# VentaConnected_Arduino_V0_01_2017-11-21.net
KiCad netlist of a schematic drawn in EAGLE
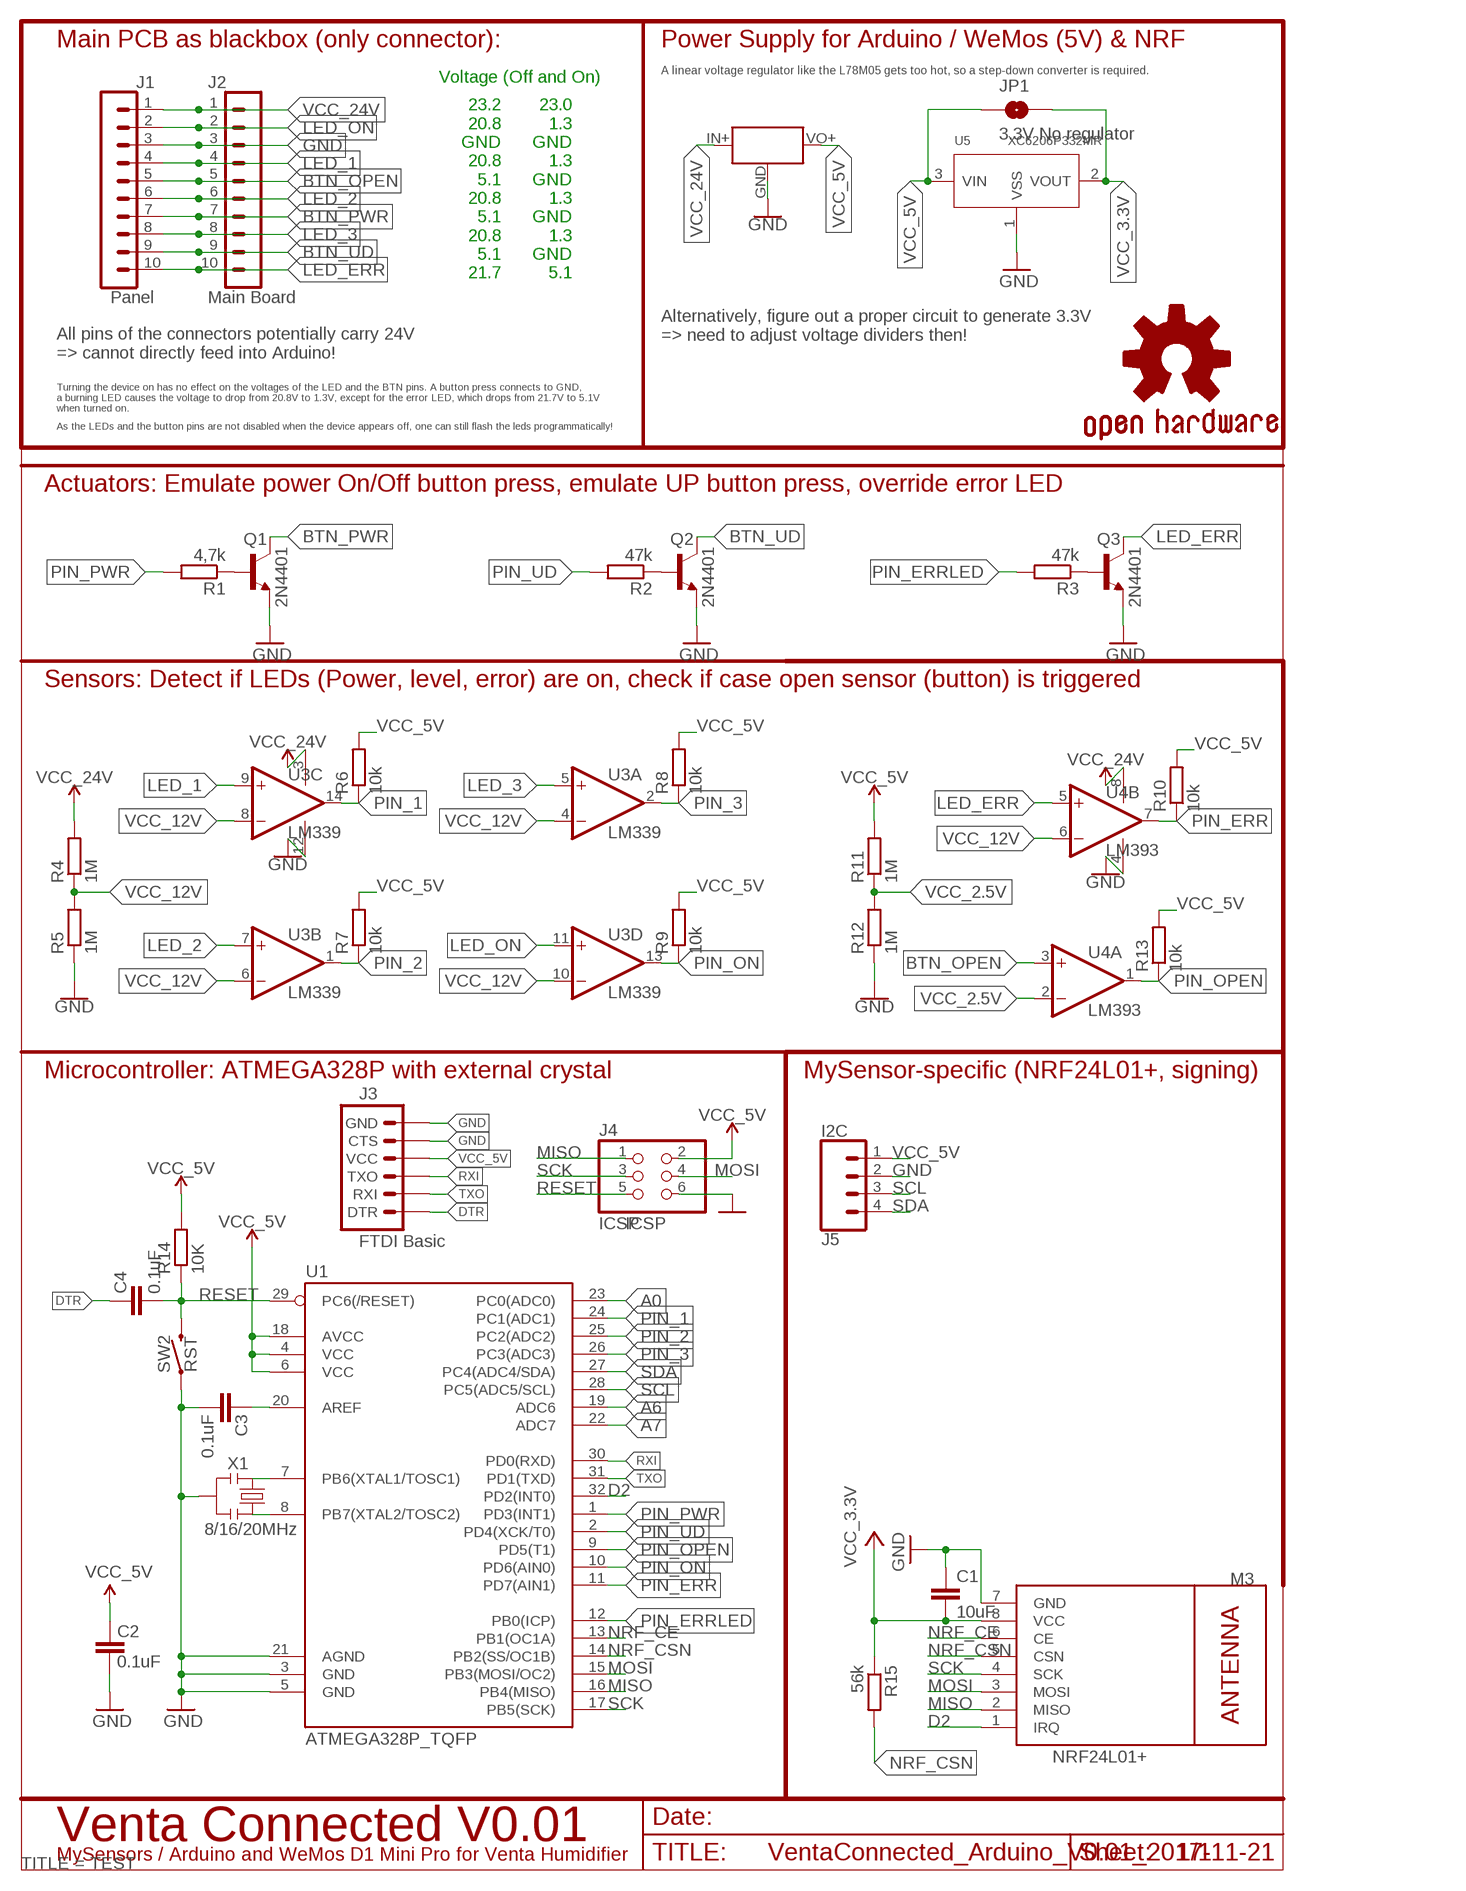
[diagram p0: schematic, sheet 1]

(export (version "E")
  (design (tool "Eeschema 10.0.6"))
  (components
    (comp (ref "C1")
      (value "10uF")
      (footprint "eagle-import:C0805")
      (libsource (lib "eagle-import") (part "C-EUC0805"))
    )
    (comp (ref "C2")
      (value "0.1uF")
      (footprint "eagle-import:0805")
      (libsource (lib "eagle-import") (part "CAP0805"))
    )
    (comp (ref "C3")
      (value "0.1uF")
      (footprint "eagle-import:0805")
      (libsource (lib "eagle-import") (part "CAP0805"))
    )
    (comp (ref "C4")
      (value "0.1uF")
      (footprint "eagle-import:0805")
      (libsource (lib "eagle-import") (part "CAP0805"))
    )
    (comp (ref "GOLD_ORB_SM1")
      (value "OSHWLOGO_GOLD_ORB_SM")
      (footprint "eagle-import:OSHW2")
      (libsource (lib "eagle-import") (part "OSHWLOGO_GOLD_ORB_SM"))
    )
    (comp (ref "J1")
      (value "Panel")
      (footprint "eagle-import:2X5-SHROUDED")
      (libsource (lib "eagle-import") (part "CONN_05X2SHD"))
    )
    (comp (ref "J2")
      (value "Main Board")
      (footprint "eagle-import:2X5")
      (libsource (lib "eagle-import") (part "CONN_05X2PTH"))
    )
    (comp (ref "J3")
      (value "FTDI Basic")
      (footprint "eagle-import:1X06")
      (libsource (lib "eagle-import") (part "ARDUINO_SERIAL_PROGRAMPTH"))
    )
    (comp (ref "J4")
      (value "ICSP")
      (footprint "eagle-import:2X03")
      (libsource (lib "eagle-import") (part "PINHD-2X3"))
    )
    (comp (ref "J5")
      (value "I2C")
      (footprint "eagle-import:1X04")
      (libsource (lib "eagle-import") (part "CONN_04"))
    )
    (comp (ref "JP1")
      (value "3.3V No regulator")
      (footprint "eagle-import:SMT-JUMPER_2_NO_SILK")
      (libsource (lib "eagle-import") (part "JUMPER-SMT_2_NO_SILK"))
    )
    (comp (ref "M3")
      (value "NRF24L01+")
      (footprint "eagle-import:WIRELESS-NRF24L01-SMD")
      (libsource (lib "eagle-import") (part "WIRELESS-NRF24L01SMD"))
    )
    (comp (ref "Q1")
      (value "2N4401")
      (footprint "eagle-import:SOT23-BEC")
      (libsource (lib "eagle-import") (part "-NPN-SOT23-BECMMBT4401LT1"))
    )
    (comp (ref "Q2")
      (value "2N4401")
      (footprint "eagle-import:SOT23-BEC")
      (libsource (lib "eagle-import") (part "-NPN-SOT23-BECMMBT4401LT1"))
    )
    (comp (ref "Q3")
      (value "2N4401")
      (footprint "eagle-import:SOT23-BEC")
      (libsource (lib "eagle-import") (part "-NPN-SOT23-BECMMBT4401LT1"))
    )
    (comp (ref "R1")
      (value "4,7k")
      (footprint "eagle-import:R0805")
      (libsource (lib "eagle-import") (part "resistor_348_R-EU_R0805"))
    )
    (comp (ref "R2")
      (value "47k")
      (footprint "eagle-import:R0805")
      (libsource (lib "eagle-import") (part "resistor_348_R-EU_R0805"))
    )
    (comp (ref "R3")
      (value "47k")
      (footprint "eagle-import:R0805")
      (libsource (lib "eagle-import") (part "resistor_348_R-EU_R0805"))
    )
    (comp (ref "R4")
      (value "1M")
      (footprint "eagle-import:R0805")
      (libsource (lib "eagle-import") (part "resistor_348_R-EU_R0805"))
    )
    (comp (ref "R5")
      (value "1M")
      (footprint "eagle-import:R0805")
      (libsource (lib "eagle-import") (part "resistor_348_R-EU_R0805"))
    )
    (comp (ref "R6")
      (value "10k")
      (footprint "eagle-import:R0805")
      (libsource (lib "eagle-import") (part "rcl_334_R-EU_R0805"))
    )
    (comp (ref "R7")
      (value "10k")
      (footprint "eagle-import:R0805")
      (libsource (lib "eagle-import") (part "rcl_334_R-EU_R0805"))
    )
    (comp (ref "R8")
      (value "10k")
      (footprint "eagle-import:R0805")
      (libsource (lib "eagle-import") (part "rcl_334_R-EU_R0805"))
    )
    (comp (ref "R9")
      (value "10k")
      (footprint "eagle-import:R0805")
      (libsource (lib "eagle-import") (part "rcl_334_R-EU_R0805"))
    )
    (comp (ref "R10")
      (value "10k")
      (footprint "eagle-import:R0805")
      (libsource (lib "eagle-import") (part "rcl_334_R-EU_R0805"))
    )
    (comp (ref "R11")
      (value "1M")
      (footprint "eagle-import:R0805")
      (libsource (lib "eagle-import") (part "resistor_348_R-EU_R0805"))
    )
    (comp (ref "R12")
      (value "1M")
      (footprint "eagle-import:R0805")
      (libsource (lib "eagle-import") (part "resistor_348_R-EU_R0805"))
    )
    (comp (ref "R13")
      (value "10k")
      (footprint "eagle-import:R0805")
      (libsource (lib "eagle-import") (part "rcl_334_R-EU_R0805"))
    )
    (comp (ref "R14")
      (value "10K")
      (footprint "eagle-import:R0805")
      (libsource (lib "eagle-import") (part "rcl_334_R-EU_R0805"))
    )
    (comp (ref "R15")
      (value "56k")
      (footprint "eagle-import:R0805")
      (libsource (lib "eagle-import") (part "R-EU_R0805"))
    )
    (comp (ref "SW2")
      (value "RST")
      (footprint "eagle-import:TACTILE_SWITCH_SMD_6.0X3.5MM")
      (libsource (lib "eagle-import") (part "MOMENTARY-SWITCH-SPST-SMD-6.0X3.5MM"))
    )
    (comp (ref "U1")
      (value "ATMEGA328P_TQFP")
      (footprint "eagle-import:TQFP32-08")
      (libsource (lib "eagle-import") (part "ATMEGA328P_TQFP"))
    )
    (comp (ref "U2")
      (value "MINI_BUCK_CONVERTER_UPSIDEDOWN")
      (footprint "eagle-import:MINI_BUCK_CONVERTER_UPDOWN")
      (libsource (lib "eagle-import") (part "MINI_BUCK_CONVERTER_UPSIDEDOWN"))
    )
    (comp (ref "U3")
      (value "LM339")
      (footprint "eagle-import:SO14")
      (libsource (lib "eagle-import") (part "TLC339D"))
    )
    (comp (ref "U4")
      (value "LM393")
      (footprint "eagle-import:SO08")
      (libsource (lib "eagle-import") (part "LM393D"))
    )
    (comp (ref "U5")
      (value "XC6206P332MR")
      (footprint "eagle-import:SOT-23")
      (fields (field (name "MPN") "XC6206P332MR-G"))
      (libsource (lib "eagle-import") (part "PMIC-LDO-XC6206P332MR-G(SOT23)"))
    )
    (comp (ref "X1")
      (value "8/16/20MHz")
      (footprint "eagle-import:RESONATOR-SMD-1_1")
      (libsource (lib "eagle-import") (part "RESONATOR1{colon}1"))
    )
  )
  (nets
    (net (code "1") (name "/D2") (class "Default")
      (node (ref "M3") (pin "1") (pinfunction "IRQ_1") (pintype "bidirectional"))
      (node (ref "U1") (pin "32") (pinfunction "PD2(INT0)_32") (pintype "bidirectional"))
    )
    (net (code "2") (name "/MISO") (class "Default")
      (node (ref "J4") (pin "1") (pinfunction "1_1") (pintype "passive"))
      (node (ref "M3") (pin "2") (pinfunction "MISO_2") (pintype "bidirectional"))
      (node (ref "U1") (pin "16") (pinfunction "PB4(MISO)_16") (pintype "bidirectional"))
    )
    (net (code "3") (name "/MOSI") (class "Default")
      (node (ref "J4") (pin "4") (pinfunction "4_4") (pintype "passive"))
      (node (ref "M3") (pin "3") (pinfunction "MOSI_3") (pintype "bidirectional"))
      (node (ref "U1") (pin "15") (pinfunction "PB3(MOSI/OC2)_15") (pintype "bidirectional"))
    )
    (net (code "4") (name "/NRF_CE") (class "Default")
      (node (ref "M3") (pin "6") (pinfunction "CE_6") (pintype "bidirectional"))
      (node (ref "U1") (pin "13") (pinfunction "PB1(OC1A)_13") (pintype "bidirectional"))
    )
    (net (code "5") (name "/RESET") (class "Default")
      (node (ref "C4") (pin "1") (pinfunction "1_1") (pintype "passive"))
      (node (ref "J4") (pin "5") (pinfunction "5_5") (pintype "passive"))
      (node (ref "R14") (pin "1") (pinfunction "1_1") (pintype "passive"))
      (node (ref "SW2") (pin "2") (pinfunction "2_2") (pintype "passive"))
      (node (ref "U1") (pin "29") (pinfunction "PC6(/RESET)_29") (pintype "bidirectional"))
    )
    (net (code "6") (name "/SCK") (class "Default")
      (node (ref "J4") (pin "3") (pinfunction "3_3") (pintype "passive"))
      (node (ref "M3") (pin "4") (pinfunction "SCK_4") (pintype "bidirectional"))
      (node (ref "U1") (pin "17") (pinfunction "PB5(SCK)_17") (pintype "bidirectional"))
    )
    (net (code "7") (name "A0") (class "Default")
      (node (ref "U1") (pin "23") (pinfunction "PC0(ADC0)_23") (pintype "bidirectional"))
    )
    (net (code "8") (name "A6") (class "Default")
      (node (ref "U1") (pin "19") (pinfunction "ADC6_19") (pintype "bidirectional"))
    )
    (net (code "9") (name "A7") (class "Default")
      (node (ref "U1") (pin "22") (pinfunction "ADC7_22") (pintype "bidirectional"))
    )
    (net (code "10") (name "BTN_OPEN") (class "Default")
      (node (ref "J1") (pin "5") (pinfunction "5_5") (pintype "passive"))
      (node (ref "J2") (pin "5") (pinfunction "5_5") (pintype "passive"))
      (node (ref "U4") (pin "3") (pinfunction "+IN_3") (pintype "input"))
    )
    (net (code "11") (name "BTN_PWR") (class "Default")
      (node (ref "J1") (pin "7") (pinfunction "7_7") (pintype "passive"))
      (node (ref "J2") (pin "7") (pinfunction "7_7") (pintype "passive"))
      (node (ref "Q1") (pin "C") (pinfunction "C_C") (pintype "passive"))
    )
    (net (code "12") (name "BTN_UD") (class "Default")
      (node (ref "J1") (pin "9") (pinfunction "9_9") (pintype "passive"))
      (node (ref "J2") (pin "9") (pinfunction "9_9") (pintype "passive"))
      (node (ref "Q2") (pin "C") (pinfunction "C_C") (pintype "passive"))
    )
    (net (code "13") (name "DTR") (class "Default")
      (node (ref "C4") (pin "2") (pinfunction "2_2") (pintype "passive"))
      (node (ref "J3") (pin "1") (pinfunction "DTR_1") (pintype "passive"))
    )
    (net (code "14") (name "GND") (class "Default")
      (node (ref "C1") (pin "1") (pinfunction "1_1") (pintype "passive"))
      (node (ref "C2") (pin "1") (pinfunction "1_1") (pintype "passive"))
      (node (ref "C3") (pin "1") (pinfunction "1_1") (pintype "passive"))
      (node (ref "J1") (pin "3") (pinfunction "3_3") (pintype "passive"))
      (node (ref "J2") (pin "3") (pinfunction "3_3") (pintype "passive"))
      (node (ref "J3") (pin "5") (pinfunction "CTS_5") (pintype "passive"))
      (node (ref "J3") (pin "6") (pinfunction "GND_6") (pintype "passive"))
      (node (ref "J4") (pin "6") (pinfunction "6_6") (pintype "passive"))
      (node (ref "J5") (pin "2") (pinfunction "2_2") (pintype "passive"))
      (node (ref "M3") (pin "7") (pinfunction "GND_7") (pintype "power_in"))
      (node (ref "Q1") (pin "E") (pinfunction "E_E") (pintype "passive"))
      (node (ref "Q2") (pin "E") (pinfunction "E_E") (pintype "passive"))
      (node (ref "Q3") (pin "E") (pinfunction "E_E") (pintype "passive"))
      (node (ref "R12") (pin "1") (pinfunction "1_1") (pintype "passive"))
      (node (ref "R5") (pin "1") (pinfunction "1_1") (pintype "passive"))
      (node (ref "SW2") (pin "1") (pinfunction "1_1") (pintype "passive"))
      (node (ref "U1") (pin "21") (pinfunction "AGND_21") (pintype "bidirectional"))
      (node (ref "U1") (pin "3") (pinfunction "GND_3") (pintype "bidirectional"))
      (node (ref "U1") (pin "5") (pinfunction "GND_5") (pintype "bidirectional"))
      (node (ref "U2") (pin "GND") (pinfunction "GND_GND") (pintype "bidirectional"))
      (node (ref "U3") (pin "12") (pinfunction "V-_12") (pintype "power_in"))
      (node (ref "U4") (pin "4") (pinfunction "V-_4") (pintype "power_in"))
      (node (ref "U5") (pin "1") (pinfunction "VSS_1") (pintype "power_in"))
      (node (ref "X1") (pin "2") (pinfunction "2_2") (pintype "passive"))
    )
    (net (code "15") (name "LED_1") (class "Default")
      (node (ref "J1") (pin "4") (pinfunction "4_4") (pintype "passive"))
      (node (ref "J2") (pin "4") (pinfunction "4_4") (pintype "passive"))
      (node (ref "U3") (pin "9") (pinfunction "+IN_9") (pintype "input"))
    )
    (net (code "16") (name "LED_2") (class "Default")
      (node (ref "J1") (pin "6") (pinfunction "6_6") (pintype "passive"))
      (node (ref "J2") (pin "6") (pinfunction "6_6") (pintype "passive"))
      (node (ref "U3") (pin "7") (pinfunction "+IN_7") (pintype "input"))
    )
    (net (code "17") (name "LED_3") (class "Default")
      (node (ref "J1") (pin "8") (pinfunction "8_8") (pintype "passive"))
      (node (ref "J2") (pin "8") (pinfunction "8_8") (pintype "passive"))
      (node (ref "U3") (pin "5") (pinfunction "+IN_5") (pintype "input"))
    )
    (net (code "18") (name "LED_ERR") (class "Default")
      (node (ref "J1") (pin "10") (pinfunction "10_10") (pintype "passive"))
      (node (ref "J2") (pin "10") (pinfunction "10_10") (pintype "passive"))
      (node (ref "Q3") (pin "C") (pinfunction "C_C") (pintype "passive"))
      (node (ref "U4") (pin "5") (pinfunction "+IN_5") (pintype "input"))
    )
    (net (code "19") (name "LED_ON") (class "Default")
      (node (ref "J1") (pin "2") (pinfunction "2_2") (pintype "passive"))
      (node (ref "J2") (pin "2") (pinfunction "2_2") (pintype "passive"))
      (node (ref "U3") (pin "11") (pinfunction "+IN_11") (pintype "input"))
    )
    (net (code "20") (name "NRF_CSN") (class "Default")
      (node (ref "M3") (pin "5") (pinfunction "CSN_5") (pintype "bidirectional"))
      (node (ref "R15") (pin "2") (pinfunction "2_2") (pintype "passive"))
      (node (ref "U1") (pin "14") (pinfunction "PB2(SS/OC1B)_14") (pintype "bidirectional"))
    )
    (net (code "21") (name "Net-(Q1-PadB)") (class "Default")
      (node (ref "Q1") (pin "B") (pinfunction "B_B") (pintype "passive"))
      (node (ref "R1") (pin "1") (pinfunction "1_1") (pintype "passive"))
    )
    (net (code "22") (name "Net-(Q2-PadB)") (class "Default")
      (node (ref "Q2") (pin "B") (pinfunction "B_B") (pintype "passive"))
      (node (ref "R2") (pin "1") (pinfunction "1_1") (pintype "passive"))
    )
    (net (code "23") (name "Net-(Q3-PadB)") (class "Default")
      (node (ref "Q3") (pin "B") (pinfunction "B_B") (pintype "passive"))
      (node (ref "R3") (pin "1") (pinfunction "1_1") (pintype "passive"))
    )
    (net (code "24") (name "Net-(U1-AREF)") (class "Default")
      (node (ref "C3") (pin "2") (pinfunction "2_2") (pintype "passive"))
      (node (ref "U1") (pin "20") (pinfunction "AREF_20") (pintype "bidirectional"))
    )
    (net (code "25") (name "Net-(U1-PB6(XTAL1{slash}TOSC1))") (class "Default")
      (node (ref "U1") (pin "7") (pinfunction "PB6(XTAL1/TOSC1)_7") (pintype "bidirectional"))
      (node (ref "X1") (pin "1") (pinfunction "1_1") (pintype "passive"))
    )
    (net (code "26") (name "Net-(U1-PB7(XTAL2{slash}TOSC2))") (class "Default")
      (node (ref "U1") (pin "8") (pinfunction "PB7(XTAL2/TOSC2)_8") (pintype "bidirectional"))
      (node (ref "X1") (pin "3") (pinfunction "3_3") (pintype "passive"))
    )
    (net (code "27") (name "PIN_1") (class "Default")
      (node (ref "R6") (pin "1") (pinfunction "1_1") (pintype "passive"))
      (node (ref "U1") (pin "24") (pinfunction "PC1(ADC1)_24") (pintype "bidirectional"))
      (node (ref "U3") (pin "14") (pinfunction "OUT_14") (pintype "output"))
    )
    (net (code "28") (name "PIN_2") (class "Default")
      (node (ref "R7") (pin "1") (pinfunction "1_1") (pintype "passive"))
      (node (ref "U1") (pin "25") (pinfunction "PC2(ADC2)_25") (pintype "bidirectional"))
      (node (ref "U3") (pin "1") (pinfunction "OUT_1") (pintype "output"))
    )
    (net (code "29") (name "PIN_3") (class "Default")
      (node (ref "R8") (pin "1") (pinfunction "1_1") (pintype "passive"))
      (node (ref "U1") (pin "26") (pinfunction "PC3(ADC3)_26") (pintype "bidirectional"))
      (node (ref "U3") (pin "2") (pinfunction "OUT_2") (pintype "output"))
    )
    (net (code "30") (name "PIN_ERR") (class "Default")
      (node (ref "R10") (pin "1") (pinfunction "1_1") (pintype "passive"))
      (node (ref "U1") (pin "11") (pinfunction "PD7(AIN1)_11") (pintype "bidirectional"))
      (node (ref "U4") (pin "7") (pinfunction "OUT_7") (pintype "output"))
    )
    (net (code "31") (name "PIN_ERRLED") (class "Default")
      (node (ref "R3") (pin "2") (pinfunction "2_2") (pintype "passive"))
      (node (ref "U1") (pin "12") (pinfunction "PB0(ICP)_12") (pintype "bidirectional"))
    )
    (net (code "32") (name "PIN_ON") (class "Default")
      (node (ref "R9") (pin "1") (pinfunction "1_1") (pintype "passive"))
      (node (ref "U1") (pin "10") (pinfunction "PD6(AIN0)_10") (pintype "bidirectional"))
      (node (ref "U3") (pin "13") (pinfunction "OUT_13") (pintype "output"))
    )
    (net (code "33") (name "PIN_OPEN") (class "Default")
      (node (ref "R13") (pin "1") (pinfunction "1_1") (pintype "passive"))
      (node (ref "U1") (pin "9") (pinfunction "PD5(T1)_9") (pintype "bidirectional"))
      (node (ref "U4") (pin "1") (pinfunction "OUT_1") (pintype "output"))
    )
    (net (code "34") (name "PIN_PWR") (class "Default")
      (node (ref "R1") (pin "2") (pinfunction "2_2") (pintype "passive"))
      (node (ref "U1") (pin "1") (pinfunction "PD3(INT1)_1") (pintype "bidirectional"))
    )
    (net (code "35") (name "PIN_UD") (class "Default")
      (node (ref "R2") (pin "2") (pinfunction "2_2") (pintype "passive"))
      (node (ref "U1") (pin "2") (pinfunction "PD4(XCK/T0)_2") (pintype "bidirectional"))
    )
    (net (code "36") (name "RXI") (class "Default")
      (node (ref "J3") (pin "3") (pinfunction "TXO_3") (pintype "passive"))
      (node (ref "U1") (pin "30") (pinfunction "PD0(RXD)_30") (pintype "bidirectional"))
    )
    (net (code "37") (name "SCL") (class "Default")
      (node (ref "J5") (pin "3") (pinfunction "3_3") (pintype "passive"))
      (node (ref "U1") (pin "28") (pinfunction "PC5(ADC5/SCL)_28") (pintype "bidirectional"))
    )
    (net (code "38") (name "SDA") (class "Default")
      (node (ref "J5") (pin "4") (pinfunction "4_4") (pintype "passive"))
      (node (ref "U1") (pin "27") (pinfunction "PC4(ADC4/SDA)_27") (pintype "bidirectional"))
    )
    (net (code "39") (name "TXO") (class "Default")
      (node (ref "J3") (pin "2") (pinfunction "RXI_2") (pintype "passive"))
      (node (ref "U1") (pin "31") (pinfunction "PD1(TXD)_31") (pintype "bidirectional"))
    )
    (net (code "40") (name "VCC_2.5V") (class "Default")
      (node (ref "R11") (pin "1") (pinfunction "1_1") (pintype "passive"))
      (node (ref "R12") (pin "2") (pinfunction "2_2") (pintype "passive"))
      (node (ref "U4") (pin "2") (pinfunction "-IN_2") (pintype "input"))
    )
    (net (code "41") (name "VCC_3.3V") (class "Default")
      (node (ref "C1") (pin "2") (pinfunction "2_2") (pintype "passive"))
      (node (ref "JP1") (pin "2") (pinfunction "2_2") (pintype "passive"))
      (node (ref "M3") (pin "8") (pinfunction "VCC_8") (pintype "power_in"))
      (node (ref "R15") (pin "1") (pinfunction "1_1") (pintype "passive"))
      (node (ref "U5") (pin "2") (pinfunction "VOUT_2") (pintype "output"))
    )
    (net (code "42") (name "VCC_5V") (class "Default")
      (node (ref "C2") (pin "2") (pinfunction "2_2") (pintype "passive"))
      (node (ref "J3") (pin "4") (pinfunction "VCC_4") (pintype "passive"))
      (node (ref "J4") (pin "2") (pinfunction "2_2") (pintype "passive"))
      (node (ref "J5") (pin "1") (pinfunction "1_1") (pintype "passive"))
      (node (ref "JP1") (pin "1") (pinfunction "1_1") (pintype "passive"))
      (node (ref "R10") (pin "2") (pinfunction "2_2") (pintype "passive"))
      (node (ref "R11") (pin "2") (pinfunction "2_2") (pintype "passive"))
      (node (ref "R13") (pin "2") (pinfunction "2_2") (pintype "passive"))
      (node (ref "R14") (pin "2") (pinfunction "2_2") (pintype "passive"))
      (node (ref "R6") (pin "2") (pinfunction "2_2") (pintype "passive"))
      (node (ref "R7") (pin "2") (pinfunction "2_2") (pintype "passive"))
      (node (ref "R8") (pin "2") (pinfunction "2_2") (pintype "passive"))
      (node (ref "R9") (pin "2") (pinfunction "2_2") (pintype "passive"))
      (node (ref "U1") (pin "18") (pinfunction "AVCC_18") (pintype "bidirectional"))
      (node (ref "U1") (pin "4") (pinfunction "VCC_4") (pintype "bidirectional"))
      (node (ref "U1") (pin "6") (pinfunction "VCC_6") (pintype "bidirectional"))
      (node (ref "U2") (pin "VO+") (pinfunction "VOUT_VO+") (pintype "power_in"))
      (node (ref "U5") (pin "3") (pinfunction "VIN_3") (pintype "input"))
    )
    (net (code "43") (name "VCC_12V") (class "Default")
      (node (ref "R4") (pin "1") (pinfunction "1_1") (pintype "passive"))
      (node (ref "R5") (pin "2") (pinfunction "2_2") (pintype "passive"))
      (node (ref "U3") (pin "10") (pinfunction "-IN_10") (pintype "input"))
      (node (ref "U3") (pin "4") (pinfunction "-IN_4") (pintype "input"))
      (node (ref "U3") (pin "6") (pinfunction "-IN_6") (pintype "input"))
      (node (ref "U3") (pin "8") (pinfunction "-IN_8") (pintype "input"))
      (node (ref "U4") (pin "6") (pinfunction "-IN_6") (pintype "input"))
    )
    (net (code "44") (name "VCC_24V") (class "Default")
      (node (ref "J1") (pin "1") (pinfunction "1_1") (pintype "passive"))
      (node (ref "J2") (pin "1") (pinfunction "1_1") (pintype "passive"))
      (node (ref "R4") (pin "2") (pinfunction "2_2") (pintype "passive"))
      (node (ref "U2") (pin "IN+") (pinfunction "VIN_IN+") (pintype "input"))
      (node (ref "U3") (pin "3") (pinfunction "V+_3") (pintype "power_in"))
      (node (ref "U4") (pin "8") (pinfunction "V+_8") (pintype "power_in"))
    )
  )
)
